# v2_0_with_IO_Expander.net
KiCad netlist of a schematic drawn in Altium Designer
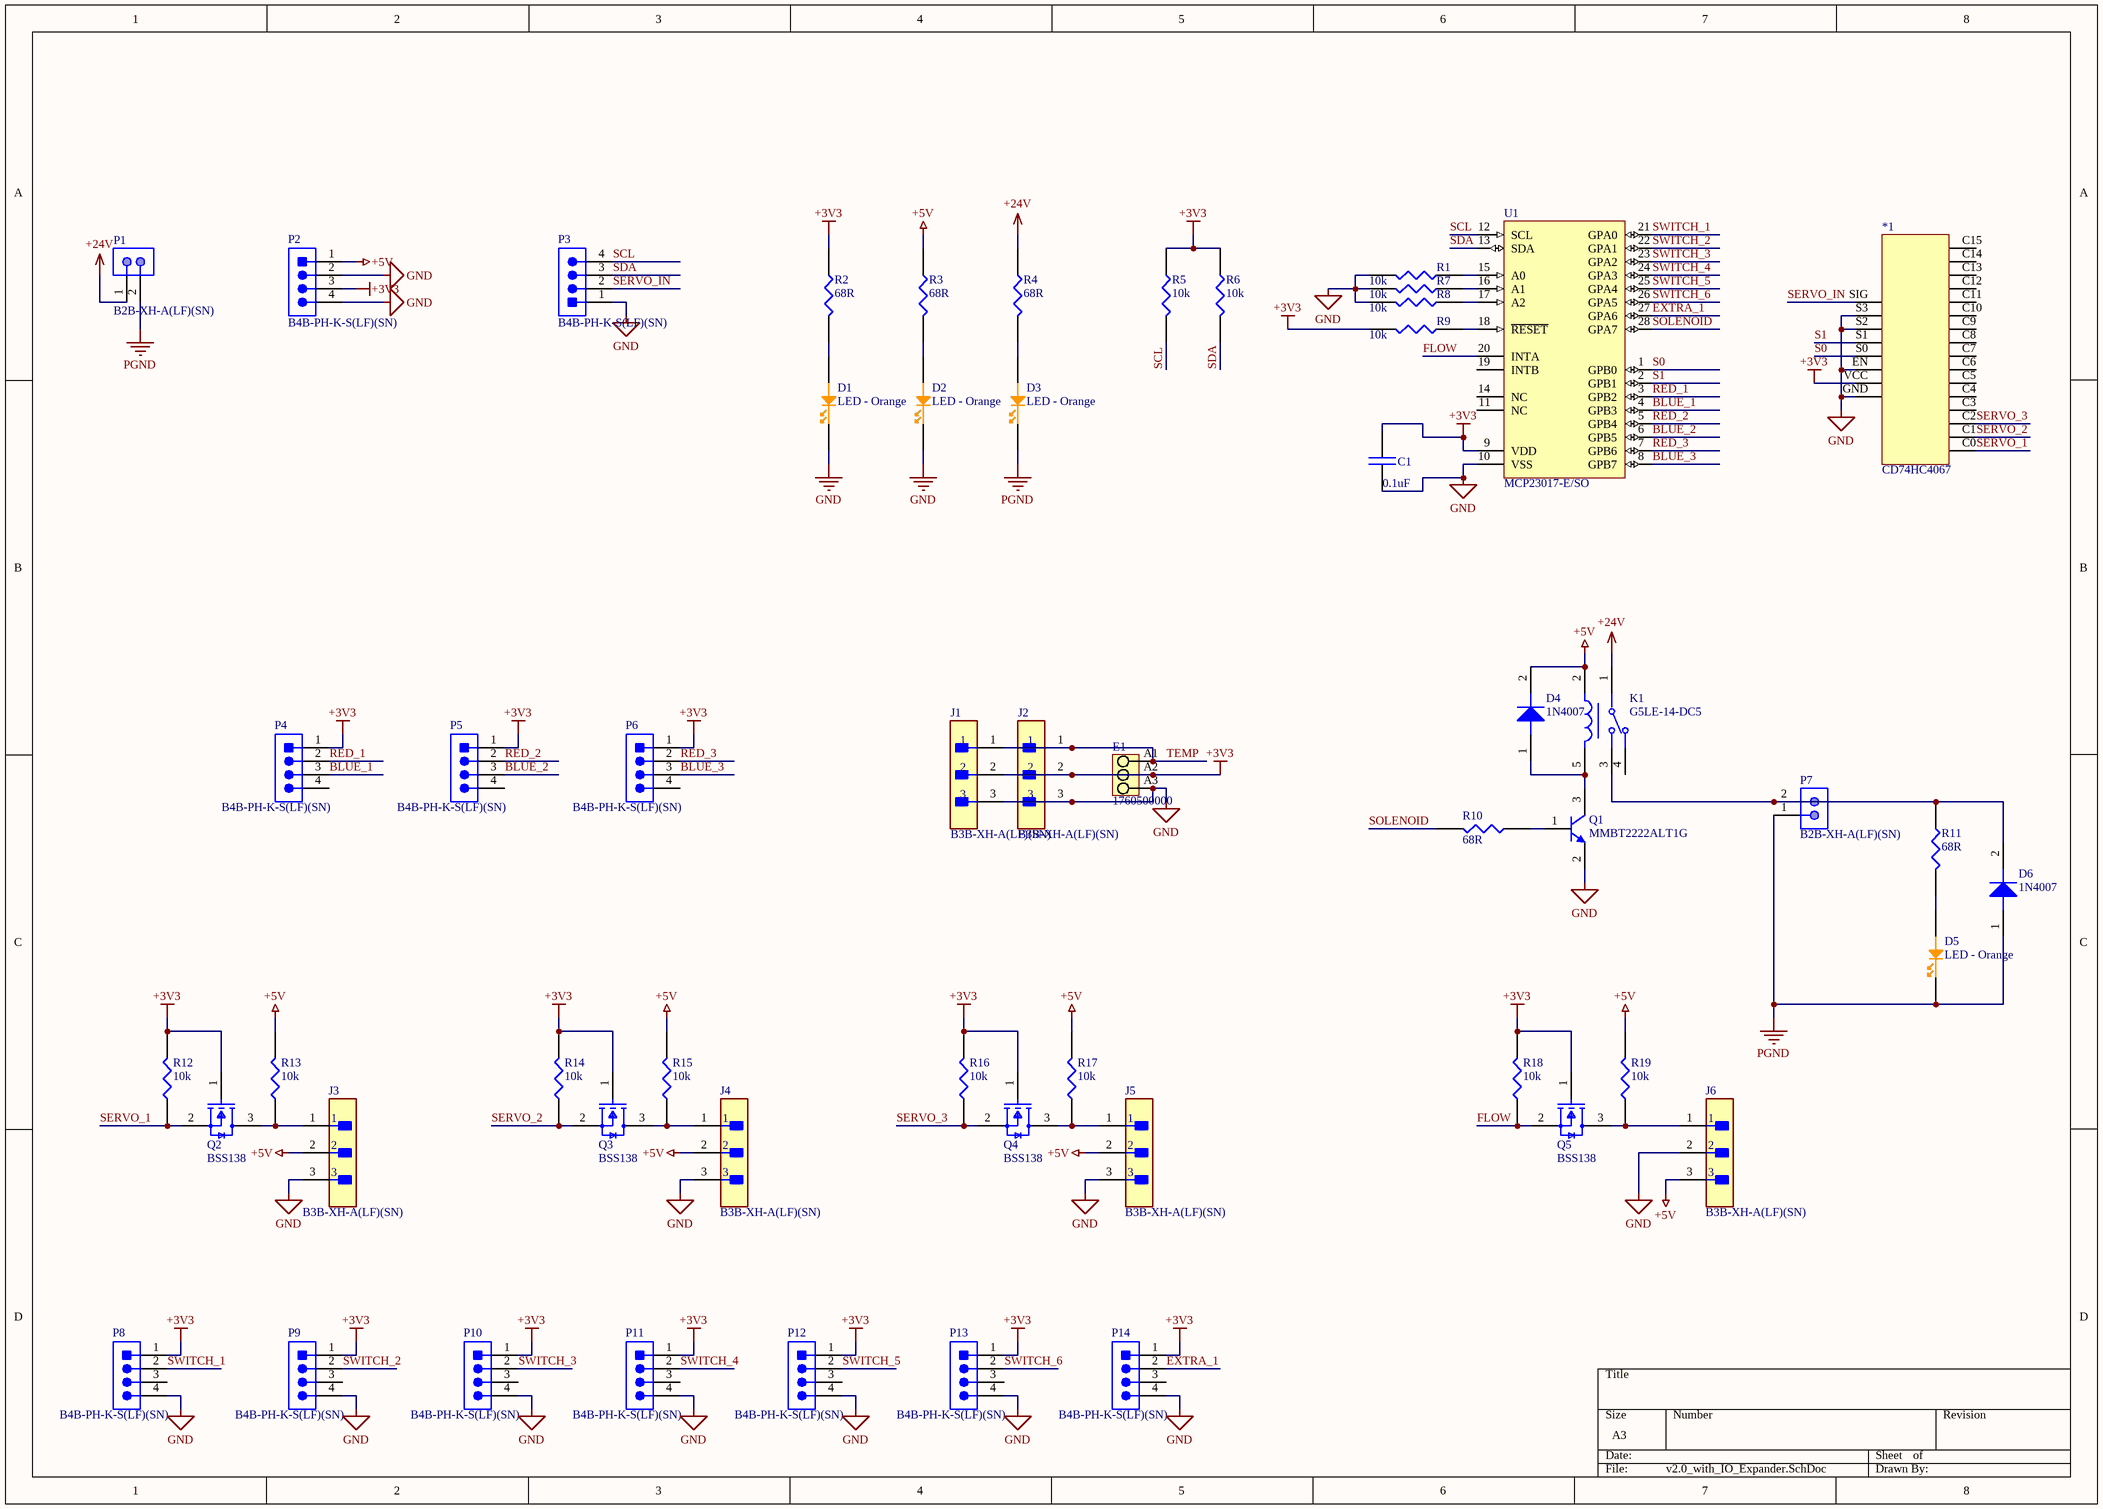
[diagram p0: v2.0_with_IO_Expander.SchDoc]

(export (version "E")
  (design (tool "Eeschema 10.0.6"))
  (components
    (comp (ref "*1")
      (value "CD74HC4067")
      (footprint "CD74HC4067 Module")
      (libsource (lib "cd74hc4067_module") (part "CD74HC4067"))
    )
    (comp (ref "C1")
      (value "0.1uF")
      (footprint "0.1uF 0603")
      (description "CAP CER 0.1UF 16V X7R 0603")
      (fields
        (field (name "MANUFACTURER") "KEMET")
        (field (name "MANUFACTURER PART NUMBER") "C0603C104M4RACTU")
      )
      (libsource (lib "Limit_Switch") (part "C0603C104M4RACTU"))
    )
    (comp (ref "D1")
      (value "LED - Orange")
      (footprint "LED0603-Orange")
      (description "LED ORANGE CLEAR SMD")
      (fields
        (field (name "MANUFACTURER") "Vishay Lite-On")
        (field (name "MANUFACTURER PART NUMBER") "LTST-C191KFKT")
      )
      (libsource (lib "Limit_Switch_RGB") (part "LTST-C191KFKT"))
    )
    (comp (ref "D2")
      (value "LED - Orange")
      (footprint "LED0603-Orange")
      (description "LED ORANGE CLEAR SMD")
      (fields
        (field (name "MANUFACTURER") "Vishay Lite-On")
        (field (name "MANUFACTURER PART NUMBER") "LTST-C191KFKT")
      )
      (libsource (lib "Limit_Switch_RGB") (part "LTST-C191KFKT"))
    )
    (comp (ref "D3")
      (value "LED - Orange")
      (footprint "LED0603-Orange")
      (description "LED ORANGE CLEAR SMD")
      (fields
        (field (name "MANUFACTURER") "Vishay Lite-On")
        (field (name "MANUFACTURER PART NUMBER") "LTST-C191KFKT")
      )
      (libsource (lib "Limit_Switch_RGB") (part "LTST-C191KFKT"))
    )
    (comp (ref "D4")
      (value "1N4007")
      (footprint "M7 1N4007 SMA")
      (description "1000V 1A Rectifier")
      (fields
        (field (name "MANUFACTURER") "Sangdest Microelectronics")
        (field (name "MANUFACTURER PART NUMBER") "1N4007FLTR")
      )
      (libsource (lib "SectionE_BreakOut") (part "1N4007FLTR"))
    )
    (comp (ref "D5")
      (value "LED - Orange")
      (footprint "LED0603-Orange")
      (description "LED ORANGE CLEAR SMD")
      (fields
        (field (name "MANUFACTURER") "Vishay Lite-On")
        (field (name "MANUFACTURER PART NUMBER") "LTST-C191KFKT")
      )
      (libsource (lib "Limit_Switch_RGB") (part "LTST-C191KFKT"))
    )
    (comp (ref "D6")
      (value "1N4007")
      (footprint "M7 1N4007 SMA")
      (description "1000V 1A Rectifier")
      (fields
        (field (name "MANUFACTURER") "Sangdest Microelectronics")
        (field (name "MANUFACTURER PART NUMBER") "1N4007FLTR")
      )
      (libsource (lib "SectionE_BreakOut") (part "1N4007FLTR"))
    )
    (comp (ref "E1")
      (value "1760500000")
      (footprint "PM_5_08_90_03")
      (description "OMNIMATE Signal - series PM")
      (fields (field (name "MANUFACTURER") "Weidmueller"))
      (libsource (lib "Altium Content Vault") (part "Terminal_03_1x03"))
    )
    (comp (ref "J1")
      (value "B3B-XH-A(LF)(SN)")
      (footprint "FP-B3B-XH-A_LF_SN-MFG")
      (description "CONN HEADER VERT 3POS 2.5MM")
      (fields
        (field (name "OCTOPART") "https://octopart.com/b3b-xh-a%28lf%29%28sn%29-jst-3990185")
        (field (name "MANUFACTURER") "JST")
      )
      (libsource (lib "") (part "0d3f023dd272f625e17a2be33dea85f_1"))
    )
    (comp (ref "J2")
      (value "B3B-XH-A(LF)(SN)")
      (footprint "FP-B3B-XH-A_LF_SN-MFG")
      (description "CONN HEADER VERT 3POS 2.5MM")
      (fields
        (field (name "OCTOPART") "https://octopart.com/b3b-xh-a%28lf%29%28sn%29-jst-3990185")
        (field (name "MANUFACTURER") "JST")
      )
      (libsource (lib "") (part "0d3f023dd272f625e17a2be33dea85f_1"))
    )
    (comp (ref "J3")
      (value "B3B-XH-A(LF)(SN)")
      (footprint "FP-B3B-XH-A_LF_SN-MFG")
      (description "CONN HEADER VERT 3POS 2.5MM")
      (fields
        (field (name "OCTOPART") "https://octopart.com/b3b-xh-a%28lf%29%28sn%29-jst-3990185")
        (field (name "MANUFACTURER") "JST")
      )
      (libsource (lib "Altium Content Vault") (part "0d3f023dd272f625e17a2be33dea85f"))
    )
    (comp (ref "J4")
      (value "B3B-XH-A(LF)(SN)")
      (footprint "FP-B3B-XH-A_LF_SN-MFG")
      (description "CONN HEADER VERT 3POS 2.5MM")
      (fields
        (field (name "OCTOPART") "https://octopart.com/b3b-xh-a%28lf%29%28sn%29-jst-3990185")
        (field (name "MANUFACTURER") "JST")
      )
      (libsource (lib "Altium Content Vault") (part "0d3f023dd272f625e17a2be33dea85f"))
    )
    (comp (ref "J5")
      (value "B3B-XH-A(LF)(SN)")
      (footprint "FP-B3B-XH-A_LF_SN-MFG")
      (description "CONN HEADER VERT 3POS 2.5MM")
      (fields
        (field (name "OCTOPART") "https://octopart.com/b3b-xh-a%28lf%29%28sn%29-jst-3990185")
        (field (name "MANUFACTURER") "JST")
      )
      (libsource (lib "Altium Content Vault") (part "0d3f023dd272f625e17a2be33dea85f"))
    )
    (comp (ref "J6")
      (value "B3B-XH-A(LF)(SN)")
      (footprint "FP-B3B-XH-A_LF_SN-MFG")
      (description "CONN HEADER VERT 3POS 2.5MM")
      (fields
        (field (name "OCTOPART") "https://octopart.com/b3b-xh-a%28lf%29%28sn%29-jst-3990185")
        (field (name "MANUFACTURER") "JST")
      )
      (libsource (lib "Altium Content Vault") (part "0d3f023dd272f625e17a2be33dea85f"))
    )
    (comp (ref "K1")
      (value "G5LE-14-DC5")
      (footprint "FP-G5LE-14-DC5-MFG")
      (description "RELAY GEN PURPOSE SPDT 10A 5V")
      (fields
        (field (name "OCTOPART") "https://octopart.com/g5le-14-dc5-omron-28829")
        (field (name "MANUFACTURER") "Omron")
      )
      (libsource (lib "Altium Content Vault") (part "c03b8d08e5d02e70a6880f365e34168"))
    )
    (comp (ref "P1")
      (value "B2B-XH-A(LF)(SN)")
      (footprint "JST-B2B-XH-A_V")
      (fields (field (name "MANUFACTURER") "JST"))
      (libsource (lib "Altium Content Vault") (part "CN-1P-M-R2"))
    )
    (comp (ref "P2")
      (value "B4B-PH-K-S(LF)(SN)")
      (footprint "JST-B4B-PH-K-S_V")
      (fields (field (name "MANUFACTURER") "JST"))
      (libsource (lib "Altium Content Vault") (part "CN-1P-M-R4"))
    )
    (comp (ref "P3")
      (value "B4B-PH-K-S(LF)(SN)")
      (footprint "JST-B4B-PH-K-S_V")
      (fields (field (name "MANUFACTURER") "JST"))
      (libsource (lib "") (part "CN-1P-M-R4_1"))
    )
    (comp (ref "P4")
      (value "B4B-PH-K-S(LF)(SN)")
      (footprint "JST-B4B-PH-K-S_V")
      (fields (field (name "MANUFACTURER") "JST"))
      (libsource (lib "Altium Content Vault") (part "CN-1P-M-R4"))
    )
    (comp (ref "P5")
      (value "B4B-PH-K-S(LF)(SN)")
      (footprint "JST-B4B-PH-K-S_V")
      (fields (field (name "MANUFACTURER") "JST"))
      (libsource (lib "Altium Content Vault") (part "CN-1P-M-R4"))
    )
    (comp (ref "P6")
      (value "B4B-PH-K-S(LF)(SN)")
      (footprint "JST-B4B-PH-K-S_V")
      (fields (field (name "MANUFACTURER") "JST"))
      (libsource (lib "Altium Content Vault") (part "CN-1P-M-R4"))
    )
    (comp (ref "P7")
      (value "B2B-XH-A(LF)(SN)")
      (footprint "JST-B2B-XH-A_V")
      (fields (field (name "MANUFACTURER") "JST"))
      (libsource (lib "Altium Content Vault") (part "CN-1P-M-R2"))
    )
    (comp (ref "P8")
      (value "B4B-PH-K-S(LF)(SN)")
      (footprint "JST-B4B-PH-K-S_V")
      (fields (field (name "MANUFACTURER") "JST"))
      (libsource (lib "Altium Content Vault") (part "CN-1P-M-R4"))
    )
    (comp (ref "P9")
      (value "B4B-PH-K-S(LF)(SN)")
      (footprint "JST-B4B-PH-K-S_V")
      (fields (field (name "MANUFACTURER") "JST"))
      (libsource (lib "Altium Content Vault") (part "CN-1P-M-R4"))
    )
    (comp (ref "P10")
      (value "B4B-PH-K-S(LF)(SN)")
      (footprint "JST-B4B-PH-K-S_V")
      (fields (field (name "MANUFACTURER") "JST"))
      (libsource (lib "Altium Content Vault") (part "CN-1P-M-R4"))
    )
    (comp (ref "P11")
      (value "B4B-PH-K-S(LF)(SN)")
      (footprint "JST-B4B-PH-K-S_V")
      (fields (field (name "MANUFACTURER") "JST"))
      (libsource (lib "Altium Content Vault") (part "CN-1P-M-R4"))
    )
    (comp (ref "P12")
      (value "B4B-PH-K-S(LF)(SN)")
      (footprint "JST-B4B-PH-K-S_V")
      (fields (field (name "MANUFACTURER") "JST"))
      (libsource (lib "Altium Content Vault") (part "CN-1P-M-R4"))
    )
    (comp (ref "P13")
      (value "B4B-PH-K-S(LF)(SN)")
      (footprint "JST-B4B-PH-K-S_V")
      (fields (field (name "MANUFACTURER") "JST"))
      (libsource (lib "Altium Content Vault") (part "CN-1P-M-R4"))
    )
    (comp (ref "P14")
      (value "B4B-PH-K-S(LF)(SN)")
      (footprint "JST-B4B-PH-K-S_V")
      (fields (field (name "MANUFACTURER") "JST"))
      (libsource (lib "Altium Content Vault") (part "CN-1P-M-R4"))
    )
    (comp (ref "Q1")
      (value "MMBT2222ALT1G")
      (footprint "ONSC-SOT-23-3-318-08_V")
      (description "General Purpose Transistor, NPN Silicon, 3-Pin SOT-23, Pb-Free, Tape and Reel")
      (fields (field (name "MANUFACTURER") "On Semiconductor"))
      (libsource (lib "Altium Content Vault") (part "ONSC-NPN-B1E2C3-3"))
    )
    (comp (ref "Q2")
      (value "BSS138")
      (footprint "FP-318-08-IPC_B")
      (description "MOSFET N-CH 50V 220MA SOT-23")
      (libsource (lib "Altium Content Vault") (part "3b9c635fedb024a5347a57b145af9cc"))
    )
    (comp (ref "Q3")
      (value "BSS138")
      (footprint "FP-318-08-IPC_B")
      (description "MOSFET N-CH 50V 220MA SOT-23")
      (libsource (lib "Altium Content Vault") (part "3b9c635fedb024a5347a57b145af9cc"))
    )
    (comp (ref "Q4")
      (value "BSS138")
      (footprint "FP-318-08-IPC_B")
      (description "MOSFET N-CH 50V 220MA SOT-23")
      (libsource (lib "Altium Content Vault") (part "3b9c635fedb024a5347a57b145af9cc"))
    )
    (comp (ref "Q5")
      (value "BSS138")
      (footprint "FP-318-08-IPC_B")
      (description "MOSFET N-CH 50V 220MA SOT-23")
      (libsource (lib "Altium Content Vault") (part "3b9c635fedb024a5347a57b145af9cc"))
    )
    (comp (ref "R1")
      (value "10k")
      (footprint "10k R0603")
      (description "RES 10.0K OHM 1/10W 1% 0603")
      (fields
        (field (name "MANUFACTURER") "TE Connectivity")
        (field (name "MANUFACTURER PART NUMBER") "CRG0603F10K/10")
      )
      (libsource (lib "Limit_Switch_RGB") (part "CRG0603F10K/10"))
    )
    (comp (ref "R2")
      (value "68R")
      (footprint "68R 0603")
      (description "CRGP 0603 68R 1%")
      (fields
        (field (name "MANUFACTURER") "TE Connectivity")
        (field (name "MANUFACTURER PART NUMBER") "CRGP0603F68R")
      )
      (libsource (lib "Limit_Switch_RGB") (part "CRGP0603F68R"))
    )
    (comp (ref "R3")
      (value "68R")
      (footprint "68R 0603")
      (description "CRGP 0603 68R 1%")
      (fields
        (field (name "MANUFACTURER") "TE Connectivity")
        (field (name "MANUFACTURER PART NUMBER") "CRGP0603F68R")
      )
      (libsource (lib "Limit_Switch_RGB") (part "CRGP0603F68R"))
    )
    (comp (ref "R4")
      (value "68R")
      (footprint "68R 0603")
      (description "CRGP 0603 68R 1%")
      (fields
        (field (name "MANUFACTURER") "TE Connectivity")
        (field (name "MANUFACTURER PART NUMBER") "CRGP0603F68R")
      )
      (libsource (lib "Limit_Switch_RGB") (part "CRGP0603F68R"))
    )
    (comp (ref "R5")
      (value "10k")
      (footprint "10k R0603")
      (description "RES 10.0K OHM 1/10W 1% 0603")
      (fields
        (field (name "MANUFACTURER") "TE Connectivity")
        (field (name "MANUFACTURER PART NUMBER") "CRG0603F10K/10")
      )
      (libsource (lib "Limit_Switch_RGB") (part "CRG0603F10K/10"))
    )
    (comp (ref "R6")
      (value "10k")
      (footprint "10k R0603")
      (description "RES 10.0K OHM 1/10W 1% 0603")
      (fields
        (field (name "MANUFACTURER") "TE Connectivity")
        (field (name "MANUFACTURER PART NUMBER") "CRG0603F10K/10")
      )
      (libsource (lib "Limit_Switch_RGB") (part "CRG0603F10K/10"))
    )
    (comp (ref "R7")
      (value "10k")
      (footprint "10k R0603")
      (description "RES 10.0K OHM 1/10W 1% 0603")
      (fields
        (field (name "MANUFACTURER") "TE Connectivity")
        (field (name "MANUFACTURER PART NUMBER") "CRG0603F10K/10")
      )
      (libsource (lib "Limit_Switch_RGB") (part "CRG0603F10K/10"))
    )
    (comp (ref "R8")
      (value "10k")
      (footprint "10k R0603")
      (description "RES 10.0K OHM 1/10W 1% 0603")
      (fields
        (field (name "MANUFACTURER") "TE Connectivity")
        (field (name "MANUFACTURER PART NUMBER") "CRG0603F10K/10")
      )
      (libsource (lib "Limit_Switch_RGB") (part "CRG0603F10K/10"))
    )
    (comp (ref "R9")
      (value "10k")
      (footprint "10k R0603")
      (description "RES 10.0K OHM 1/10W 1% 0603")
      (fields
        (field (name "MANUFACTURER") "TE Connectivity")
        (field (name "MANUFACTURER PART NUMBER") "CRG0603F10K/10")
      )
      (libsource (lib "Limit_Switch_RGB") (part "CRG0603F10K/10"))
    )
    (comp (ref "R10")
      (value "68R")
      (footprint "68R 0603")
      (description "CRGP 0603 68R 1%")
      (fields
        (field (name "MANUFACTURER") "TE Connectivity")
        (field (name "MANUFACTURER PART NUMBER") "CRGP0603F68R")
      )
      (libsource (lib "Limit_Switch_RGB") (part "CRGP0603F68R"))
    )
    (comp (ref "R11")
      (value "68R")
      (footprint "68R 0603")
      (description "CRGP 0603 68R 1%")
      (fields
        (field (name "MANUFACTURER") "TE Connectivity")
        (field (name "MANUFACTURER PART NUMBER") "CRGP0603F68R")
      )
      (libsource (lib "Limit_Switch_RGB") (part "CRGP0603F68R"))
    )
    (comp (ref "R12")
      (value "10k")
      (footprint "10k R0603")
      (description "RES 10.0K OHM 1/10W 1% 0603")
      (fields
        (field (name "MANUFACTURER") "TE Connectivity")
        (field (name "MANUFACTURER PART NUMBER") "CRG0603F10K/10")
      )
      (libsource (lib "Limit_Switch_RGB") (part "CRG0603F10K/10"))
    )
    (comp (ref "R13")
      (value "10k")
      (footprint "10k R0603")
      (description "RES 10.0K OHM 1/10W 1% 0603")
      (fields
        (field (name "MANUFACTURER") "TE Connectivity")
        (field (name "MANUFACTURER PART NUMBER") "CRG0603F10K/10")
      )
      (libsource (lib "Limit_Switch_RGB") (part "CRG0603F10K/10"))
    )
    (comp (ref "R14")
      (value "10k")
      (footprint "10k R0603")
      (description "RES 10.0K OHM 1/10W 1% 0603")
      (fields
        (field (name "MANUFACTURER") "TE Connectivity")
        (field (name "MANUFACTURER PART NUMBER") "CRG0603F10K/10")
      )
      (libsource (lib "Limit_Switch_RGB") (part "CRG0603F10K/10"))
    )
    (comp (ref "R15")
      (value "10k")
      (footprint "10k R0603")
      (description "RES 10.0K OHM 1/10W 1% 0603")
      (fields
        (field (name "MANUFACTURER") "TE Connectivity")
        (field (name "MANUFACTURER PART NUMBER") "CRG0603F10K/10")
      )
      (libsource (lib "Limit_Switch_RGB") (part "CRG0603F10K/10"))
    )
    (comp (ref "R16")
      (value "10k")
      (footprint "10k R0603")
      (description "RES 10.0K OHM 1/10W 1% 0603")
      (fields
        (field (name "MANUFACTURER") "TE Connectivity")
        (field (name "MANUFACTURER PART NUMBER") "CRG0603F10K/10")
      )
      (libsource (lib "Limit_Switch_RGB") (part "CRG0603F10K/10"))
    )
    (comp (ref "R17")
      (value "10k")
      (footprint "10k R0603")
      (description "RES 10.0K OHM 1/10W 1% 0603")
      (fields
        (field (name "MANUFACTURER") "TE Connectivity")
        (field (name "MANUFACTURER PART NUMBER") "CRG0603F10K/10")
      )
      (libsource (lib "Limit_Switch_RGB") (part "CRG0603F10K/10"))
    )
    (comp (ref "R18")
      (value "10k")
      (footprint "10k R0603")
      (description "RES 10.0K OHM 1/10W 1% 0603")
      (fields
        (field (name "MANUFACTURER") "TE Connectivity")
        (field (name "MANUFACTURER PART NUMBER") "CRG0603F10K/10")
      )
      (libsource (lib "Limit_Switch_RGB") (part "CRG0603F10K/10"))
    )
    (comp (ref "R19")
      (value "10k")
      (footprint "10k R0603")
      (description "RES 10.0K OHM 1/10W 1% 0603")
      (fields
        (field (name "MANUFACTURER") "TE Connectivity")
        (field (name "MANUFACTURER PART NUMBER") "CRG0603F10K/10")
      )
      (libsource (lib "Limit_Switch_RGB") (part "CRG0603F10K/10"))
    )
    (comp (ref "U1")
      (value "MCP23017-E/SO")
      (footprint "SOIC-SO28_N")
      (description "16-Bit I/O Expander with Serial Interface, 28-Pin SOIC, Extended Temperature")
      (libsource (lib "Altium Content Vault") (part "PR-BUSIC-MCP23017-28"))
    )
  )
  (nets
    (net (code "1") (name "+3V3") (class "Default")
      (node (ref "*1") (pin "VCC") (pinfunction "C17_VCC") (pintype "passive"))
      (node (ref "C1") (pin "1") (pinfunction "1_1") (pintype "passive"))
      (node (ref "E1") (pin "A2") (pinfunction "A2_A2") (pintype "passive"))
      (node (ref "J1") (pin "2") (pinfunction "2_2") (pintype "passive"))
      (node (ref "J2") (pin "2") (pinfunction "2_2") (pintype "passive"))
      (node (ref "P10") (pin "1") (pinfunction "1_1") (pintype "passive"))
      (node (ref "P11") (pin "1") (pinfunction "1_1") (pintype "passive"))
      (node (ref "P12") (pin "1") (pinfunction "1_1") (pintype "passive"))
      (node (ref "P13") (pin "1") (pinfunction "1_1") (pintype "passive"))
      (node (ref "P14") (pin "1") (pinfunction "1_1") (pintype "passive"))
      (node (ref "P2") (pin "3") (pinfunction "3_3") (pintype "passive"))
      (node (ref "P4") (pin "1") (pinfunction "1_1") (pintype "passive"))
      (node (ref "P5") (pin "1") (pinfunction "1_1") (pintype "passive"))
      (node (ref "P6") (pin "1") (pinfunction "1_1") (pintype "passive"))
      (node (ref "P8") (pin "1") (pinfunction "1_1") (pintype "passive"))
      (node (ref "P9") (pin "1") (pinfunction "1_1") (pintype "passive"))
      (node (ref "Q2") (pin "1") (pinfunction "G_1") (pintype "passive"))
      (node (ref "Q3") (pin "1") (pinfunction "G_1") (pintype "passive"))
      (node (ref "Q4") (pin "1") (pinfunction "G_1") (pintype "passive"))
      (node (ref "Q5") (pin "1") (pinfunction "G_1") (pintype "passive"))
      (node (ref "R12") (pin "2") (pinfunction "2_2") (pintype "passive"))
      (node (ref "R14") (pin "2") (pinfunction "2_2") (pintype "passive"))
      (node (ref "R16") (pin "2") (pinfunction "2_2") (pintype "passive"))
      (node (ref "R18") (pin "2") (pinfunction "2_2") (pintype "passive"))
      (node (ref "R2") (pin "1") (pinfunction "1_1") (pintype "passive"))
      (node (ref "R5") (pin "1") (pinfunction "1_1") (pintype "passive"))
      (node (ref "R6") (pin "1") (pinfunction "1_1") (pintype "passive"))
      (node (ref "R9") (pin "2") (pinfunction "2_2") (pintype "passive"))
      (node (ref "U1") (pin "9") (pinfunction "VDD_9") (pintype "power_in"))
    )
    (net (code "2") (name "+5V") (class "Default")
      (node (ref "D4") (pin "2") (pinfunction "Cathode_2") (pintype "passive"))
      (node (ref "J3") (pin "2") (pinfunction "2_2") (pintype "passive"))
      (node (ref "J4") (pin "2") (pinfunction "2_2") (pintype "passive"))
      (node (ref "J5") (pin "2") (pinfunction "2_2") (pintype "passive"))
      (node (ref "J6") (pin "3") (pinfunction "3_3") (pintype "passive"))
      (node (ref "K1") (pin "2") (pinfunction "2_2") (pintype "passive"))
      (node (ref "P2") (pin "1") (pinfunction "1_1") (pintype "passive"))
      (node (ref "R13") (pin "2") (pinfunction "2_2") (pintype "passive"))
      (node (ref "R15") (pin "2") (pinfunction "2_2") (pintype "passive"))
      (node (ref "R17") (pin "2") (pinfunction "2_2") (pintype "passive"))
      (node (ref "R19") (pin "2") (pinfunction "2_2") (pintype "passive"))
      (node (ref "R3") (pin "1") (pinfunction "1_1") (pintype "passive"))
    )
    (net (code "3") (name "+24V") (class "Default")
      (node (ref "K1") (pin "1") (pinfunction "1_1") (pintype "passive"))
      (node (ref "P1") (pin "1") (pinfunction "1_1") (pintype "passive"))
      (node (ref "R4") (pin "1") (pinfunction "1_1") (pintype "passive"))
    )
    (net (code "4") (name "/BLUE_1") (class "Default")
      (node (ref "P4") (pin "3") (pinfunction "3_3") (pintype "passive"))
      (node (ref "U1") (pin "4") (pinfunction "GPB3_4") (pintype "bidirectional"))
    )
    (net (code "5") (name "/BLUE_2") (class "Default")
      (node (ref "P5") (pin "3") (pinfunction "3_3") (pintype "passive"))
      (node (ref "U1") (pin "6") (pinfunction "GPB5_6") (pintype "bidirectional"))
    )
    (net (code "6") (name "/BLUE_3") (class "Default")
      (node (ref "P6") (pin "3") (pinfunction "3_3") (pintype "passive"))
      (node (ref "U1") (pin "8") (pinfunction "GPB7_8") (pintype "bidirectional"))
    )
    (net (code "7") (name "/EXTRA_1") (class "Default")
      (node (ref "P14") (pin "2") (pinfunction "2_2") (pintype "passive"))
      (node (ref "U1") (pin "27") (pinfunction "GPA6_27") (pintype "bidirectional"))
    )
    (net (code "8") (name "/FLOW") (class "Default")
      (node (ref "Q5") (pin "2") (pinfunction "S_2") (pintype "passive"))
      (node (ref "R18") (pin "1") (pinfunction "1_1") (pintype "passive"))
      (node (ref "U1") (pin "20") (pinfunction "INTA_20") (pintype "open_collector"))
    )
    (net (code "9") (name "/RED_1") (class "Default")
      (node (ref "P4") (pin "2") (pinfunction "2_2") (pintype "passive"))
      (node (ref "U1") (pin "3") (pinfunction "GPB2_3") (pintype "bidirectional"))
    )
    (net (code "10") (name "/RED_2") (class "Default")
      (node (ref "P5") (pin "2") (pinfunction "2_2") (pintype "passive"))
      (node (ref "U1") (pin "5") (pinfunction "GPB4_5") (pintype "bidirectional"))
    )
    (net (code "11") (name "/RED_3") (class "Default")
      (node (ref "P6") (pin "2") (pinfunction "2_2") (pintype "passive"))
      (node (ref "U1") (pin "7") (pinfunction "GPB6_7") (pintype "bidirectional"))
    )
    (net (code "12") (name "/S0") (class "Default")
      (node (ref "*1") (pin "S0") (pinfunction "C19_S0") (pintype "passive"))
      (node (ref "U1") (pin "1") (pinfunction "GPB0_1") (pintype "bidirectional"))
    )
    (net (code "13") (name "/S1") (class "Default")
      (node (ref "*1") (pin "S1") (pinfunction "C20_S1") (pintype "passive"))
      (node (ref "U1") (pin "2") (pinfunction "GPB1_2") (pintype "bidirectional"))
    )
    (net (code "14") (name "/SCL") (class "Default")
      (node (ref "P3") (pin "4") (pinfunction "4_4") (pintype "passive"))
      (node (ref "R5") (pin "2") (pinfunction "2_2") (pintype "passive"))
      (node (ref "U1") (pin "12") (pinfunction "SCL_12") (pintype "input"))
    )
    (net (code "15") (name "/SDA") (class "Default")
      (node (ref "P3") (pin "3") (pinfunction "3_3") (pintype "passive"))
      (node (ref "R6") (pin "2") (pinfunction "2_2") (pintype "passive"))
      (node (ref "U1") (pin "13") (pinfunction "SDA_13") (pintype "bidirectional"))
    )
    (net (code "16") (name "/SERVO_1") (class "Default")
      (node (ref "*1") (pin "C0") (pinfunction "1_C0") (pintype "passive"))
      (node (ref "Q2") (pin "2") (pinfunction "S_2") (pintype "passive"))
      (node (ref "R12") (pin "1") (pinfunction "1_1") (pintype "passive"))
    )
    (net (code "17") (name "/SERVO_2") (class "Default")
      (node (ref "*1") (pin "C1") (pinfunction "2_C1") (pintype "passive"))
      (node (ref "Q3") (pin "2") (pinfunction "S_2") (pintype "passive"))
      (node (ref "R14") (pin "1") (pinfunction "1_1") (pintype "passive"))
    )
    (net (code "18") (name "/SERVO_3") (class "Default")
      (node (ref "*1") (pin "C2") (pinfunction "3_C2") (pintype "passive"))
      (node (ref "Q4") (pin "2") (pinfunction "S_2") (pintype "passive"))
      (node (ref "R16") (pin "1") (pinfunction "1_1") (pintype "passive"))
    )
    (net (code "19") (name "/SERVO_IN") (class "Default")
      (node (ref "*1") (pin "SIG") (pinfunction "C23_SIG") (pintype "passive"))
      (node (ref "P3") (pin "2") (pinfunction "2_2") (pintype "passive"))
    )
    (net (code "20") (name "/SOLENOID") (class "Default")
      (node (ref "R10") (pin "2") (pinfunction "2_2") (pintype "passive"))
      (node (ref "U1") (pin "28") (pinfunction "GPA7_28") (pintype "bidirectional"))
    )
    (net (code "21") (name "/SWITCH_1") (class "Default")
      (node (ref "P8") (pin "2") (pinfunction "2_2") (pintype "passive"))
      (node (ref "U1") (pin "21") (pinfunction "GPA0_21") (pintype "bidirectional"))
    )
    (net (code "22") (name "/SWITCH_2") (class "Default")
      (node (ref "P9") (pin "2") (pinfunction "2_2") (pintype "passive"))
      (node (ref "U1") (pin "22") (pinfunction "GPA1_22") (pintype "bidirectional"))
    )
    (net (code "23") (name "/SWITCH_3") (class "Default")
      (node (ref "P10") (pin "2") (pinfunction "2_2") (pintype "passive"))
      (node (ref "U1") (pin "23") (pinfunction "GPA2_23") (pintype "bidirectional"))
    )
    (net (code "24") (name "/SWITCH_4") (class "Default")
      (node (ref "P11") (pin "2") (pinfunction "2_2") (pintype "passive"))
      (node (ref "U1") (pin "24") (pinfunction "GPA3_24") (pintype "bidirectional"))
    )
    (net (code "25") (name "/SWITCH_5") (class "Default")
      (node (ref "P12") (pin "2") (pinfunction "2_2") (pintype "passive"))
      (node (ref "U1") (pin "25") (pinfunction "GPA4_25") (pintype "bidirectional"))
    )
    (net (code "26") (name "/SWITCH_6") (class "Default")
      (node (ref "P13") (pin "2") (pinfunction "2_2") (pintype "passive"))
      (node (ref "U1") (pin "26") (pinfunction "GPA5_26") (pintype "bidirectional"))
    )
    (net (code "27") (name "/TEMP") (class "Default")
      (node (ref "E1") (pin "A1") (pinfunction "A1_A1") (pintype "passive"))
      (node (ref "J1") (pin "1") (pinfunction "1_1") (pintype "passive"))
      (node (ref "J2") (pin "1") (pinfunction "1_1") (pintype "passive"))
    )
    (net (code "28") (name "GND") (class "Default")
      (node (ref "*1") (pin "EN") (pinfunction "C18_EN") (pintype "passive"))
      (node (ref "*1") (pin "GND") (pinfunction "C16_GND") (pintype "passive"))
      (node (ref "*1") (pin "S2") (pinfunction "C21_S2") (pintype "passive"))
      (node (ref "*1") (pin "S3") (pinfunction "C22_S3") (pintype "passive"))
      (node (ref "C1") (pin "2") (pinfunction "2_2") (pintype "passive"))
      (node (ref "D1") (pin "1") (pinfunction "Cathode_1") (pintype "passive"))
      (node (ref "D2") (pin "1") (pinfunction "Cathode_1") (pintype "passive"))
      (node (ref "E1") (pin "A3") (pinfunction "A3_A3") (pintype "passive"))
      (node (ref "J1") (pin "3") (pinfunction "3_3") (pintype "passive"))
      (node (ref "J2") (pin "3") (pinfunction "3_3") (pintype "passive"))
      (node (ref "J3") (pin "3") (pinfunction "3_3") (pintype "passive"))
      (node (ref "J4") (pin "3") (pinfunction "3_3") (pintype "passive"))
      (node (ref "J5") (pin "3") (pinfunction "3_3") (pintype "passive"))
      (node (ref "J6") (pin "2") (pinfunction "2_2") (pintype "passive"))
      (node (ref "P10") (pin "4") (pinfunction "4_4") (pintype "passive"))
      (node (ref "P11") (pin "4") (pinfunction "4_4") (pintype "passive"))
      (node (ref "P12") (pin "4") (pinfunction "4_4") (pintype "passive"))
      (node (ref "P13") (pin "4") (pinfunction "4_4") (pintype "passive"))
      (node (ref "P14") (pin "4") (pinfunction "4_4") (pintype "passive"))
      (node (ref "P2") (pin "2") (pinfunction "2_2") (pintype "passive"))
      (node (ref "P2") (pin "4") (pinfunction "4_4") (pintype "passive"))
      (node (ref "P3") (pin "1") (pinfunction "1_1") (pintype "passive"))
      (node (ref "P8") (pin "4") (pinfunction "4_4") (pintype "passive"))
      (node (ref "P9") (pin "4") (pinfunction "4_4") (pintype "passive"))
      (node (ref "Q1") (pin "2") (pinfunction "E_2") (pintype "passive"))
      (node (ref "R1") (pin "2") (pinfunction "2_2") (pintype "passive"))
      (node (ref "R7") (pin "2") (pinfunction "2_2") (pintype "passive"))
      (node (ref "R8") (pin "2") (pinfunction "2_2") (pintype "passive"))
      (node (ref "U1") (pin "10") (pinfunction "VSS_10") (pintype "power_in"))
    )
    (net (code "29") (name "Net-(D1-Anode)") (class "Default")
      (node (ref "D1") (pin "2") (pinfunction "Anode_2") (pintype "passive"))
      (node (ref "R2") (pin "2") (pinfunction "2_2") (pintype "passive"))
    )
    (net (code "30") (name "Net-(D2-Anode)") (class "Default")
      (node (ref "D2") (pin "2") (pinfunction "Anode_2") (pintype "passive"))
      (node (ref "R3") (pin "2") (pinfunction "2_2") (pintype "passive"))
    )
    (net (code "31") (name "Net-(D3-Anode)") (class "Default")
      (node (ref "D3") (pin "2") (pinfunction "Anode_2") (pintype "passive"))
      (node (ref "R4") (pin "2") (pinfunction "2_2") (pintype "passive"))
    )
    (net (code "32") (name "Net-(D4-Anode)") (class "Default")
      (node (ref "D4") (pin "1") (pinfunction "Anode_1") (pintype "passive"))
      (node (ref "K1") (pin "5") (pinfunction "5_5") (pintype "passive"))
      (node (ref "Q1") (pin "3") (pinfunction "C_3") (pintype "passive"))
    )
    (net (code "33") (name "Net-(D5-Anode)") (class "Default")
      (node (ref "D5") (pin "2") (pinfunction "Anode_2") (pintype "passive"))
      (node (ref "R11") (pin "2") (pinfunction "2_2") (pintype "passive"))
    )
    (net (code "34") (name "Net-(D6-Cathode)") (class "Default")
      (node (ref "D6") (pin "2") (pinfunction "Cathode_2") (pintype "passive"))
      (node (ref "K1") (pin "3") (pinfunction "3_3") (pintype "passive"))
      (node (ref "P7") (pin "2") (pinfunction "2_2") (pintype "passive"))
      (node (ref "R11") (pin "1") (pinfunction "1_1") (pintype "passive"))
    )
    (net (code "35") (name "Net-(Q1-B)") (class "Default")
      (node (ref "Q1") (pin "1") (pinfunction "B_1") (pintype "passive"))
      (node (ref "R10") (pin "1") (pinfunction "1_1") (pintype "passive"))
    )
    (net (code "36") (name "Net-(Q2-D)") (class "Default")
      (node (ref "J3") (pin "1") (pinfunction "1_1") (pintype "passive"))
      (node (ref "Q2") (pin "3") (pinfunction "D_3") (pintype "passive"))
      (node (ref "R13") (pin "1") (pinfunction "1_1") (pintype "passive"))
    )
    (net (code "37") (name "Net-(Q3-D)") (class "Default")
      (node (ref "J4") (pin "1") (pinfunction "1_1") (pintype "passive"))
      (node (ref "Q3") (pin "3") (pinfunction "D_3") (pintype "passive"))
      (node (ref "R15") (pin "1") (pinfunction "1_1") (pintype "passive"))
    )
    (net (code "38") (name "Net-(Q4-D)") (class "Default")
      (node (ref "J5") (pin "1") (pinfunction "1_1") (pintype "passive"))
      (node (ref "Q4") (pin "3") (pinfunction "D_3") (pintype "passive"))
      (node (ref "R17") (pin "1") (pinfunction "1_1") (pintype "passive"))
    )
    (net (code "39") (name "Net-(Q5-D)") (class "Default")
      (node (ref "J6") (pin "1") (pinfunction "1_1") (pintype "passive"))
      (node (ref "Q5") (pin "3") (pinfunction "D_3") (pintype "passive"))
      (node (ref "R19") (pin "1") (pinfunction "1_1") (pintype "passive"))
    )
    (net (code "40") (name "Net-(U1-A0)") (class "Default")
      (node (ref "R1") (pin "1") (pinfunction "1_1") (pintype "passive"))
      (node (ref "U1") (pin "15") (pinfunction "A0_15") (pintype "input"))
    )
    (net (code "41") (name "Net-(U1-A1)") (class "Default")
      (node (ref "R7") (pin "1") (pinfunction "1_1") (pintype "passive"))
      (node (ref "U1") (pin "16") (pinfunction "A1_16") (pintype "input"))
    )
    (net (code "42") (name "Net-(U1-A2)") (class "Default")
      (node (ref "R8") (pin "1") (pinfunction "1_1") (pintype "passive"))
      (node (ref "U1") (pin "17") (pinfunction "A2_17") (pintype "input"))
    )
    (net (code "43") (name "Net-(U1-~{RESET})") (class "Default")
      (node (ref "R9") (pin "1") (pinfunction "1_1") (pintype "passive"))
      (node (ref "U1") (pin "18") (pinfunction "~{RESET}_18") (pintype "input"))
    )
    (net (code "44") (name "PGND") (class "Default")
      (node (ref "D3") (pin "1") (pinfunction "Cathode_1") (pintype "passive"))
      (node (ref "D5") (pin "1") (pinfunction "Cathode_1") (pintype "passive"))
      (node (ref "D6") (pin "1") (pinfunction "Anode_1") (pintype "passive"))
      (node (ref "P1") (pin "2") (pinfunction "2_2") (pintype "passive"))
      (node (ref "P7") (pin "1") (pinfunction "1_1") (pintype "passive"))
    )
    (net (code "45") (name "unconnected-(*1-4-PadC3)") (class "Default")
      (node (ref "*1") (pin "C3") (pinfunction "4_C3") (pintype "passive"))
    )
    (net (code "46") (name "unconnected-(*1-5-PadC4)") (class "Default")
      (node (ref "*1") (pin "C4") (pinfunction "5_C4") (pintype "passive"))
    )
    (net (code "47") (name "unconnected-(*1-6-PadC5)") (class "Default")
      (node (ref "*1") (pin "C5") (pinfunction "6_C5") (pintype "passive"))
    )
    (net (code "48") (name "unconnected-(*1-7-PadC6)") (class "Default")
      (node (ref "*1") (pin "C6") (pinfunction "7_C6") (pintype "passive"))
    )
    (net (code "49") (name "unconnected-(*1-8-PadC7)") (class "Default")
      (node (ref "*1") (pin "C7") (pinfunction "8_C7") (pintype "passive"))
    )
    (net (code "50") (name "unconnected-(*1-9-PadC8)") (class "Default")
      (node (ref "*1") (pin "C8") (pinfunction "9_C8") (pintype "passive"))
    )
    (net (code "51") (name "unconnected-(*1-10-PadC9)") (class "Default")
      (node (ref "*1") (pin "C9") (pinfunction "10_C9") (pintype "passive"))
    )
    (net (code "52") (name "unconnected-(*1-11-PadC10)") (class "Default")
      (node (ref "*1") (pin "C10") (pinfunction "11_C10") (pintype "passive"))
    )
    (net (code "53") (name "unconnected-(*1-12-PadC11)") (class "Default")
      (node (ref "*1") (pin "C11") (pinfunction "12_C11") (pintype "passive"))
    )
    (net (code "54") (name "unconnected-(*1-13-PadC12)") (class "Default")
      (node (ref "*1") (pin "C12") (pinfunction "13_C12") (pintype "passive"))
    )
    (net (code "55") (name "unconnected-(*1-14-PadC13)") (class "Default")
      (node (ref "*1") (pin "C13") (pinfunction "14_C13") (pintype "passive"))
    )
    (net (code "56") (name "unconnected-(*1-15-PadC14)") (class "Default")
      (node (ref "*1") (pin "C14") (pinfunction "15_C14") (pintype "passive"))
    )
    (net (code "57") (name "unconnected-(*1-16-PadC15)") (class "Default")
      (node (ref "*1") (pin "C15") (pinfunction "16_C15") (pintype "passive"))
    )
    (net (code "58") (name "unconnected-(K1-Pad4)") (class "Default")
      (node (ref "K1") (pin "4") (pinfunction "4_4") (pintype "passive"))
    )
    (net (code "59") (name "unconnected-(P4-Pad4)") (class "Default")
      (node (ref "P4") (pin "4") (pinfunction "4_4") (pintype "passive"))
    )
    (net (code "60") (name "unconnected-(P5-Pad4)") (class "Default")
      (node (ref "P5") (pin "4") (pinfunction "4_4") (pintype "passive"))
    )
    (net (code "61") (name "unconnected-(P6-Pad4)") (class "Default")
      (node (ref "P6") (pin "4") (pinfunction "4_4") (pintype "passive"))
    )
    (net (code "62") (name "unconnected-(P8-Pad3)") (class "Default")
      (node (ref "P8") (pin "3") (pinfunction "3_3") (pintype "passive"))
    )
    (net (code "63") (name "unconnected-(P9-Pad3)") (class "Default")
      (node (ref "P9") (pin "3") (pinfunction "3_3") (pintype "passive"))
    )
    (net (code "64") (name "unconnected-(P10-Pad3)") (class "Default")
      (node (ref "P10") (pin "3") (pinfunction "3_3") (pintype "passive"))
    )
    (net (code "65") (name "unconnected-(P11-Pad3)") (class "Default")
      (node (ref "P11") (pin "3") (pinfunction "3_3") (pintype "passive"))
    )
    (net (code "66") (name "unconnected-(P12-Pad3)") (class "Default")
      (node (ref "P12") (pin "3") (pinfunction "3_3") (pintype "passive"))
    )
    (net (code "67") (name "unconnected-(P13-Pad3)") (class "Default")
      (node (ref "P13") (pin "3") (pinfunction "3_3") (pintype "passive"))
    )
    (net (code "68") (name "unconnected-(P14-Pad3)") (class "Default")
      (node (ref "P14") (pin "3") (pinfunction "3_3") (pintype "passive"))
    )
    (net (code "69") (name "unconnected-(U1-INTB-Pad19)") (class "Default")
      (node (ref "U1") (pin "19") (pinfunction "INTB_19") (pintype "open_collector"))
    )
    (net (code "70") (name "unconnected-(U1-NC-Pad11)") (class "Default")
      (node (ref "U1") (pin "11") (pinfunction "NC_11") (pintype "passive"))
    )
    (net (code "71") (name "unconnected-(U1-NC-Pad14)") (class "Default")
      (node (ref "U1") (pin "14") (pinfunction "NC_14") (pintype "passive"))
    )
  )
)
